# contact_control_board_smd.net
KiCad netlist of a schematic drawn in EAGLE
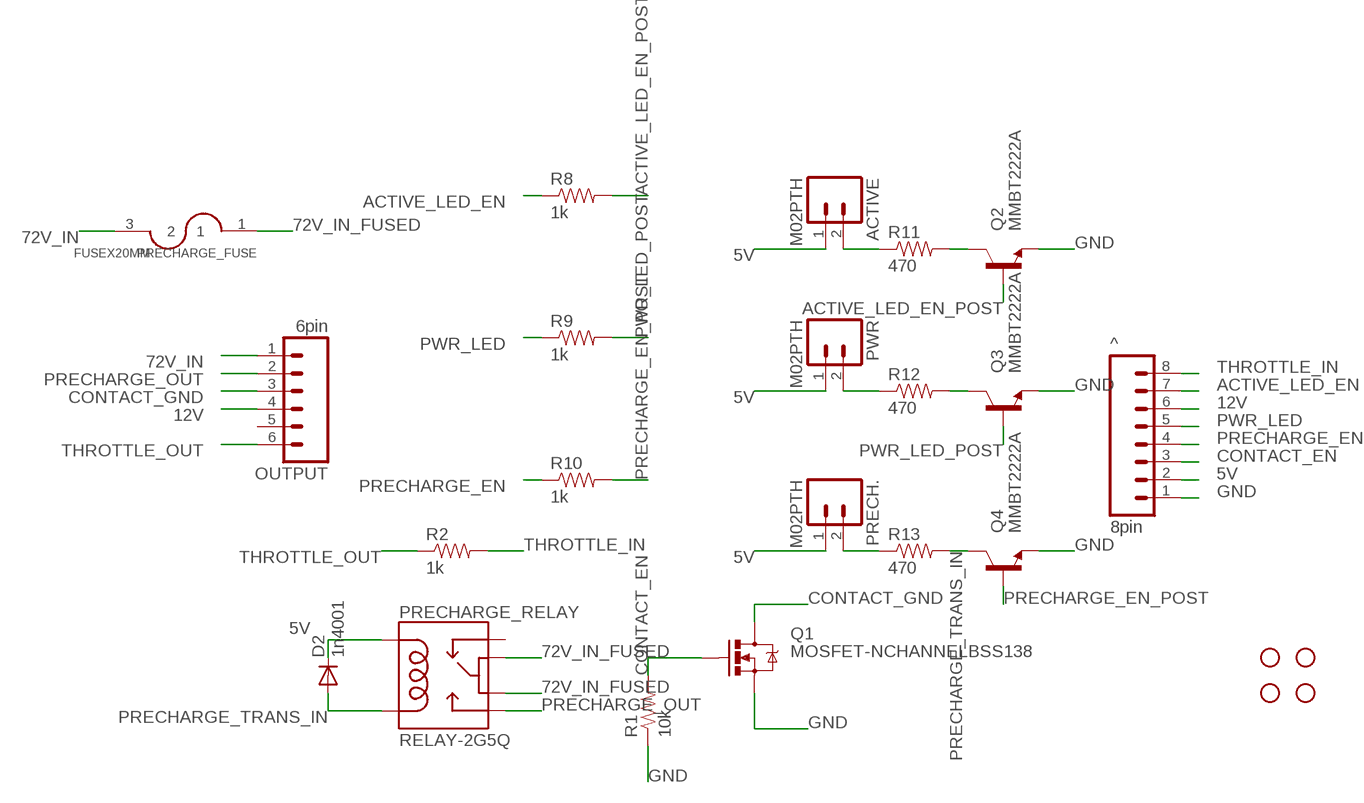
[diagram p0: schematic, sheet 1]

(export (version "E")
  (design (tool "Eeschema 10.0.6"))
  (components
    (comp (ref "ACTIVE")
      (value "M02PTH")
      (footprint "eagle-import:1X02")
      (libsource (lib "eagle-import") (part "M02PTH"))
    )
    (comp (ref "D2")
      (value "1n4001")
      (footprint "eagle-import:SMA-DIODE")
      (libsource (lib "eagle-import") (part "DIODESMA"))
    )
    (comp (ref "OUTPUT")
      (value "6pin")
      (footprint "eagle-import:SCREWTERMINAL-3.5MM-6")
      (libsource (lib "eagle-import") (part "M063.5MM-6"))
    )
    (comp (ref "PRECH.")
      (value "M02PTH")
      (footprint "eagle-import:1X02")
      (libsource (lib "eagle-import") (part "M02PTH"))
    )
    (comp (ref "PRECHARGE_FUSE")
      (value "FUSEX20MM")
      (footprint "eagle-import:FUSE_5MM")
      (libsource (lib "eagle-import") (part "FUSEX20MM"))
    )
    (comp (ref "PRECHARGE_RELAY")
      (value "RELAY-2G5Q")
      (footprint "eagle-import:RELAY-G5V")
      (libsource (lib "eagle-import") (part "RELAY-2G5Q"))
    )
    (comp (ref "PWR")
      (value "M02PTH")
      (footprint "eagle-import:1X02")
      (libsource (lib "eagle-import") (part "M02PTH"))
    )
    (comp (ref "Q1")
      (value "MOSFET-NCHANNELBSS138")
      (footprint "eagle-import:SOT23")
      (libsource (lib "eagle-import") (part "MOSFET-NCHANNELBSS138"))
    )
    (comp (ref "Q2")
      (value "MMBT2222A")
      (footprint "eagle-import:SOT23")
      (libsource (lib "eagle-import") (part "TRANSISTOR_NPNMMBT2222A"))
    )
    (comp (ref "Q3")
      (value "MMBT2222A")
      (footprint "eagle-import:SOT23")
      (libsource (lib "eagle-import") (part "TRANSISTOR_NPNMMBT2222A"))
    )
    (comp (ref "Q4")
      (value "MMBT2222A")
      (footprint "eagle-import:SOT23")
      (libsource (lib "eagle-import") (part "TRANSISTOR_NPNMMBT2222A"))
    )
    (comp (ref "R1")
      (value "10k")
      (footprint "eagle-import:0603-RES")
      (libsource (lib "eagle-import") (part "RESISTOR0603"))
    )
    (comp (ref "R2")
      (value "1k")
      (footprint "eagle-import:0603-RES")
      (libsource (lib "eagle-import") (part "RESISTOR0603-RES"))
    )
    (comp (ref "R8")
      (value "1k")
      (footprint "eagle-import:0603-RES")
      (libsource (lib "eagle-import") (part "RESISTOR0603"))
    )
    (comp (ref "R9")
      (value "1k")
      (footprint "eagle-import:0603-RES")
      (libsource (lib "eagle-import") (part "RESISTOR0603"))
    )
    (comp (ref "R10")
      (value "1k")
      (footprint "eagle-import:0603-RES")
      (libsource (lib "eagle-import") (part "RESISTOR0603"))
    )
    (comp (ref "R11")
      (value "470")
      (footprint "eagle-import:0603-RES")
      (libsource (lib "eagle-import") (part "RESISTOR0603"))
    )
    (comp (ref "R12")
      (value "470")
      (footprint "eagle-import:0603-RES")
      (libsource (lib "eagle-import") (part "RESISTOR0603"))
    )
    (comp (ref "R13")
      (value "470")
      (footprint "eagle-import:0603-RES")
      (libsource (lib "eagle-import") (part "RESISTOR0603"))
    )
    (comp (ref "STANDOFF1")
      (value "STAND-OFF")
      (footprint "eagle-import:STAND-OFF")
      (libsource (lib "eagle-import") (part "STAND-OFF"))
    )
    (comp (ref "STANDOFF2")
      (value "STAND-OFF")
      (footprint "eagle-import:STAND-OFF")
      (libsource (lib "eagle-import") (part "STAND-OFF"))
    )
    (comp (ref "STANDOFF3")
      (value "STAND-OFF")
      (footprint "eagle-import:STAND-OFF")
      (libsource (lib "eagle-import") (part "STAND-OFF"))
    )
    (comp (ref "STANDOFF4")
      (value "STAND-OFF")
      (footprint "eagle-import:STAND-OFF")
      (libsource (lib "eagle-import") (part "STAND-OFF"))
    )
    (comp (ref "^")
      (value "8pin")
      (footprint "eagle-import:1X08")
      (libsource (lib "eagle-import") (part "M081X08"))
    )
  )
  (nets
    (net (code "1") (name "/5V") (class "Default")
      (node (ref "ACTIVE") (pin "1") (pinfunction "1_1") (pintype "passive"))
      (node (ref "D2") (pin "C") (pinfunction "C_C") (pintype "passive"))
      (node (ref "PRECH.") (pin "1") (pinfunction "1_1") (pintype "passive"))
      (node (ref "PRECHARGE_RELAY") (pin "2") (pinfunction "2_2") (pintype "bidirectional"))
      (node (ref "PWR") (pin "1") (pinfunction "1_1") (pintype "passive"))
      (node (ref "^") (pin "2") (pinfunction "2_2") (pintype "passive"))
    )
    (net (code "2") (name "/12V") (class "Default")
      (node (ref "OUTPUT") (pin "4") (pinfunction "4_4") (pintype "passive"))
      (node (ref "^") (pin "6") (pinfunction "6_6") (pintype "passive"))
    )
    (net (code "3") (name "/72V_IN") (class "Default")
      (node (ref "OUTPUT") (pin "1") (pinfunction "1_1") (pintype "passive"))
      (node (ref "PRECHARGE_FUSE") (pin "3") (pinfunction "2_3") (pintype "bidirectional"))
    )
    (net (code "4") (name "/72V_IN_FUSED") (class "Default")
      (node (ref "PRECHARGE_FUSE") (pin "1") (pinfunction "1_1") (pintype "bidirectional"))
      (node (ref "PRECHARGE_RELAY") (pin "5") (pinfunction "5_5") (pintype "bidirectional"))
      (node (ref "PRECHARGE_RELAY") (pin "6") (pinfunction "6_6") (pintype "bidirectional"))
    )
    (net (code "5") (name "/ACTIVE_LED_EN") (class "Default")
      (node (ref "R8") (pin "1") (pinfunction "1_1") (pintype "passive"))
      (node (ref "^") (pin "7") (pinfunction "7_7") (pintype "passive"))
    )
    (net (code "6") (name "/ACTIVE_LED_EN_POST") (class "Default")
      (node (ref "Q2") (pin "1") (pinfunction "B_1") (pintype "passive"))
      (node (ref "R8") (pin "2") (pinfunction "2_2") (pintype "passive"))
    )
    (net (code "7") (name "/CONTACT_EN") (class "Default")
      (node (ref "Q1") (pin "1") (pinfunction "G_1") (pintype "passive"))
      (node (ref "R1") (pin "2") (pinfunction "2_2") (pintype "passive"))
      (node (ref "^") (pin "3") (pinfunction "3_3") (pintype "passive"))
    )
    (net (code "8") (name "/CONTACT_GND") (class "Default")
      (node (ref "OUTPUT") (pin "3") (pinfunction "3_3") (pintype "passive"))
      (node (ref "Q1") (pin "3") (pinfunction "D_3") (pintype "passive"))
    )
    (net (code "9") (name "/GND") (class "Default")
      (node (ref "Q1") (pin "2") (pinfunction "S_2") (pintype "passive"))
      (node (ref "Q2") (pin "2") (pinfunction "E_2") (pintype "passive"))
      (node (ref "Q3") (pin "2") (pinfunction "E_2") (pintype "passive"))
      (node (ref "Q4") (pin "2") (pinfunction "E_2") (pintype "passive"))
      (node (ref "R1") (pin "1") (pinfunction "1_1") (pintype "passive"))
      (node (ref "^") (pin "1") (pinfunction "1_1") (pintype "passive"))
    )
    (net (code "10") (name "/PRECHARGE_EN") (class "Default")
      (node (ref "R10") (pin "1") (pinfunction "1_1") (pintype "passive"))
      (node (ref "^") (pin "4") (pinfunction "4_4") (pintype "passive"))
    )
    (net (code "11") (name "/PRECHARGE_EN_POST") (class "Default")
      (node (ref "Q4") (pin "1") (pinfunction "B_1") (pintype "passive"))
      (node (ref "R10") (pin "2") (pinfunction "2_2") (pintype "passive"))
    )
    (net (code "12") (name "/PRECHARGE_OUT") (class "Default")
      (node (ref "OUTPUT") (pin "2") (pinfunction "2_2") (pintype "passive"))
      (node (ref "PRECHARGE_RELAY") (pin "10") (pinfunction "10_10") (pintype "bidirectional"))
    )
    (net (code "13") (name "/PRECHARGE_TRANS_IN") (class "Default")
      (node (ref "D2") (pin "A") (pinfunction "A_A") (pintype "passive"))
      (node (ref "PRECHARGE_RELAY") (pin "9") (pinfunction "9_9") (pintype "bidirectional"))
      (node (ref "Q4") (pin "3") (pinfunction "C_3") (pintype "passive"))
      (node (ref "R13") (pin "2") (pinfunction "2_2") (pintype "passive"))
    )
    (net (code "14") (name "/PWR_LED") (class "Default")
      (node (ref "R9") (pin "1") (pinfunction "1_1") (pintype "passive"))
      (node (ref "^") (pin "5") (pinfunction "5_5") (pintype "passive"))
    )
    (net (code "15") (name "/PWR_LED_POST") (class "Default")
      (node (ref "Q3") (pin "1") (pinfunction "B_1") (pintype "passive"))
      (node (ref "R9") (pin "2") (pinfunction "2_2") (pintype "passive"))
    )
    (net (code "16") (name "/THROTTLE_IN") (class "Default")
      (node (ref "R2") (pin "2") (pinfunction "2_2") (pintype "passive"))
      (node (ref "^") (pin "8") (pinfunction "8_8") (pintype "passive"))
    )
    (net (code "17") (name "/THROTTLE_OUT") (class "Default")
      (node (ref "OUTPUT") (pin "6") (pinfunction "6_6") (pintype "passive"))
      (node (ref "R2") (pin "1") (pinfunction "1_1") (pintype "passive"))
    )
    (net (code "18") (name "Net-(ACTIVE-Pad2)") (class "Default")
      (node (ref "ACTIVE") (pin "2") (pinfunction "2_2") (pintype "passive"))
      (node (ref "R11") (pin "1") (pinfunction "1_1") (pintype "passive"))
    )
    (net (code "19") (name "Net-(PRECH.-Pad2)") (class "Default")
      (node (ref "PRECH.") (pin "2") (pinfunction "2_2") (pintype "passive"))
      (node (ref "R13") (pin "1") (pinfunction "1_1") (pintype "passive"))
    )
    (net (code "20") (name "Net-(PWR-Pad2)") (class "Default")
      (node (ref "PWR") (pin "2") (pinfunction "2_2") (pintype "passive"))
      (node (ref "R12") (pin "1") (pinfunction "1_1") (pintype "passive"))
    )
    (net (code "21") (name "Net-(Q2-C)") (class "Default")
      (node (ref "Q2") (pin "3") (pinfunction "C_3") (pintype "passive"))
      (node (ref "R11") (pin "2") (pinfunction "2_2") (pintype "passive"))
    )
    (net (code "22") (name "Net-(Q3-C)") (class "Default")
      (node (ref "Q3") (pin "3") (pinfunction "C_3") (pintype "passive"))
      (node (ref "R12") (pin "2") (pinfunction "2_2") (pintype "passive"))
    )
    (net (code "23") (name "unconnected-(OUTPUT-Pad5)") (class "Default")
      (node (ref "OUTPUT") (pin "5") (pinfunction "5_5") (pintype "passive"))
    )
    (net (code "24") (name "unconnected-(PRECHARGE_RELAY-Pad1)") (class "Default")
      (node (ref "PRECHARGE_RELAY") (pin "1") (pinfunction "1_1") (pintype "bidirectional"))
    )
  )
)
